# Backpage.net
KiCad netlist of a schematic drawn in Altium Designer
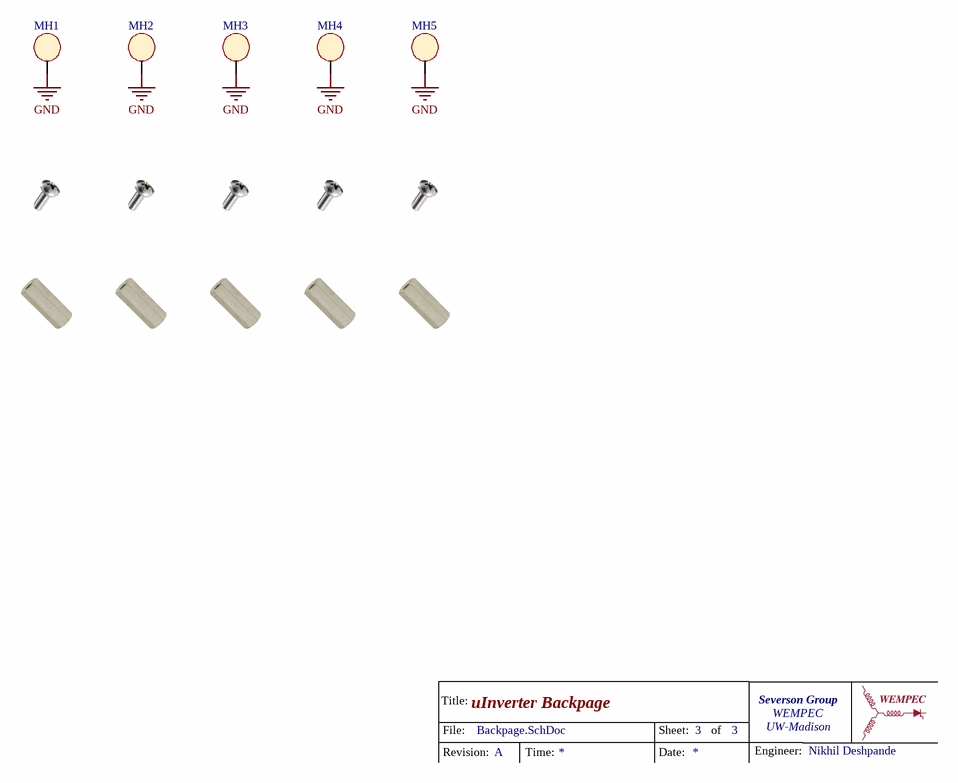
[diagram p0: Backpage.SchDoc]

(export (version "E")
  (design (tool "Eeschema 10.0.6"))
  (components
    (comp (ref "MH1")
      (value "MOUNT_HOLE")
      (footprint "MOUNTING_HOLE")
      (description "MOUNTING HOLE")
      (libsource (lib "Schlib_uInv01") (part "MOUNT_HOLE"))
    )
    (comp (ref "MH2")
      (value "MOUNT_HOLE")
      (footprint "MOUNTING_HOLE")
      (description "MOUNTING HOLE")
      (libsource (lib "Schlib_uInv01") (part "MOUNT_HOLE"))
    )
    (comp (ref "MH3")
      (value "MOUNT_HOLE")
      (footprint "MOUNTING_HOLE")
      (description "MOUNTING HOLE")
      (libsource (lib "Schlib_uInv01") (part "MOUNT_HOLE"))
    )
    (comp (ref "MH4")
      (value "MOUNT_HOLE")
      (footprint "MOUNTING_HOLE")
      (description "MOUNTING HOLE")
      (libsource (lib "Schlib_uInv01") (part "MOUNT_HOLE"))
    )
    (comp (ref "MH5")
      (value "MOUNT_HOLE")
      (footprint "MOUNTING_HOLE")
      (description "MOUNTING HOLE")
      (libsource (lib "Schlib_uInv01") (part "MOUNT_HOLE"))
    )
    (comp (ref "SCREW1") (value "Screw-4-40") (libsource (lib "Schlib_uInv01") (part "Screw-4-40")))
    (comp (ref "SCREW2") (value "Screw-4-40") (libsource (lib "Schlib_uInv01") (part "Screw-4-40")))
    (comp (ref "SCREW3") (value "Screw-4-40") (libsource (lib "Schlib_uInv01") (part "Screw-4-40")))
    (comp (ref "SCREW4") (value "Screw-4-40") (libsource (lib "Schlib_uInv01") (part "Screw-4-40")))
    (comp (ref "SCREW5") (value "Screw-4-40") (libsource (lib "Schlib_uInv01") (part "Screw-4-40")))
    (comp (ref "STANDOFF1") (value "Standoff-4-40") (libsource (lib "Schlib_uInv01") (part "Standoff-4-40")))
    (comp (ref "STANDOFF2") (value "Standoff-4-40") (libsource (lib "Schlib_uInv01") (part "Standoff-4-40")))
    (comp (ref "STANDOFF3") (value "Standoff-4-40") (libsource (lib "Schlib_uInv01") (part "Standoff-4-40")))
    (comp (ref "STANDOFF4") (value "Standoff-4-40") (libsource (lib "Schlib_uInv01") (part "Standoff-4-40")))
    (comp (ref "STANDOFF5") (value "Standoff-4-40") (libsource (lib "Schlib_uInv01") (part "Standoff-4-40")))
    (comp (ref "TitleBlockWEMPEC3")
      (value "TitleBlockWEMPEC")
      (libsource (lib "Schlib_uInv01") (part "TitleBlockWEMPEC"))
    )
  )
  (nets
    (net (code "1") (name "GND") (class "Default")
      (node (ref "MH1") (pin "1") (pinfunction "1_1") (pintype "passive"))
      (node (ref "MH2") (pin "1") (pinfunction "1_1") (pintype "passive"))
      (node (ref "MH3") (pin "1") (pinfunction "1_1") (pintype "passive"))
      (node (ref "MH4") (pin "1") (pinfunction "1_1") (pintype "passive"))
      (node (ref "MH5") (pin "1") (pinfunction "1_1") (pintype "passive"))
    )
  )
)
